# l_meter.net
KiCad netlist of a schematic drawn in EAGLE
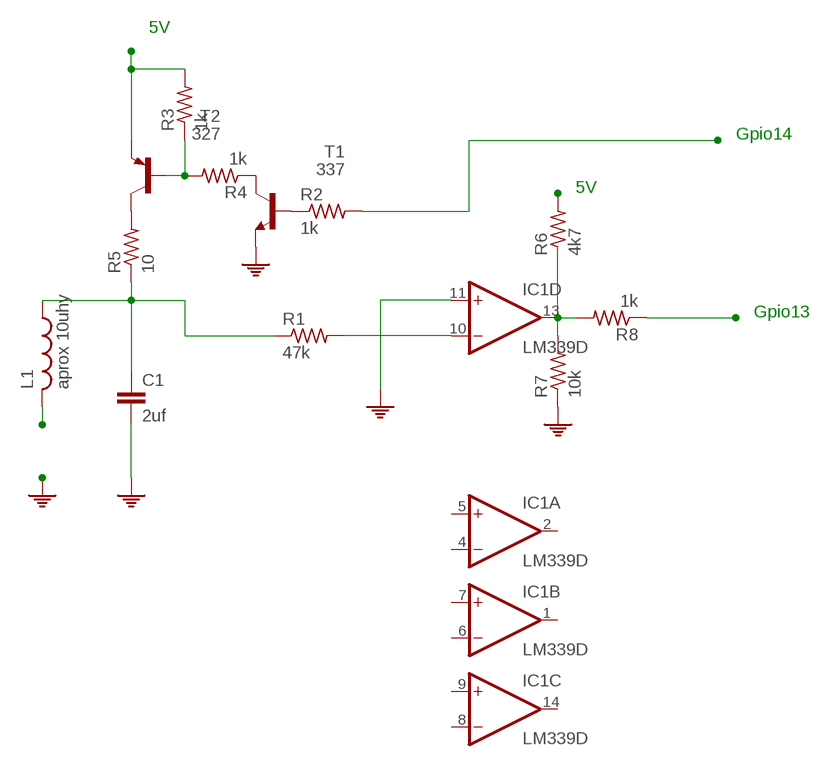
[diagram p0: schematic, sheet 1]

(export (version "E")
  (design (tool "Eeschema 10.0.6"))
  (components
    (comp (ref "C1")
      (value "2uf")
      (footprint "eagle-import:C025-030X050")
      (libsource (lib "eagle-import") (part "C-EU025-030X050"))
    )
    (comp (ref "IC1")
      (value "LM339D")
      (footprint "eagle-import:SO14")
      (libsource (lib "eagle-import") (part "LM339D"))
    )
    (comp (ref "L1")
      (value "aprox 10uhy")
      (footprint "eagle-import:IRF46")
      (libsource (lib "eagle-import") (part "L-USIRF-46"))
    )
    (comp (ref "R1")
      (value "47k")
      (footprint "eagle-import:0207_10")
      (libsource (lib "eagle-import") (part "R-US_0207/10"))
    )
    (comp (ref "R2")
      (value "1k")
      (footprint "eagle-import:0207_10")
      (libsource (lib "eagle-import") (part "R-US_0207/10"))
    )
    (comp (ref "R3")
      (value "1k")
      (footprint "eagle-import:0207_10")
      (libsource (lib "eagle-import") (part "R-US_0207/10"))
    )
    (comp (ref "R4")
      (value "1k")
      (footprint "eagle-import:0207_10")
      (libsource (lib "eagle-import") (part "R-US_0207/10"))
    )
    (comp (ref "R5")
      (value "10")
      (footprint "eagle-import:0207_10")
      (libsource (lib "eagle-import") (part "R-US_0207/10"))
    )
    (comp (ref "R6")
      (value "4k7")
      (footprint "eagle-import:0207_10")
      (libsource (lib "eagle-import") (part "R-US_0207/10"))
    )
    (comp (ref "R7")
      (value "10k")
      (footprint "eagle-import:0207_10")
      (libsource (lib "eagle-import") (part "R-US_0207/10"))
    )
    (comp (ref "R8")
      (value "1k")
      (footprint "eagle-import:0207_10")
      (libsource (lib "eagle-import") (part "R-US_0207/10"))
    )
    (comp (ref "T1")
      (value "337")
      (footprint "eagle-import:SOT23-EBC")
      (libsource (lib "eagle-import") (part "-NPN-SOT23-EBC"))
    )
    (comp (ref "T2")
      (value "327")
      (footprint "eagle-import:TO92")
      (libsource (lib "eagle-import") (part "-PNP-TO92"))
    )
  )
  (nets
    (net (code "1") (name "Net-(C1-Pad1)") (class "Default")
      (node (ref "C1") (pin "1") (pinfunction "1_1") (pintype "passive"))
      (node (ref "L1") (pin "1") (pinfunction "1_1") (pintype "passive"))
      (node (ref "R1") (pin "1") (pinfunction "1_1") (pintype "passive"))
      (node (ref "R5") (pin "1") (pinfunction "1_1") (pintype "passive"))
    )
    (net (code "2") (name "Net-(IC1D--IN)") (class "Default")
      (node (ref "IC1") (pin "10") (pinfunction "-IN_10") (pintype "input"))
      (node (ref "R1") (pin "2") (pinfunction "2_2") (pintype "passive"))
    )
    (net (code "3") (name "Net-(IC1D-OUT)") (class "Default")
      (node (ref "IC1") (pin "13") (pinfunction "OUT_13") (pintype "open_collector"))
      (node (ref "R7") (pin "2") (pinfunction "2_2") (pintype "passive"))
      (node (ref "R8") (pin "2") (pinfunction "2_2") (pintype "passive"))
    )
    (net (code "4") (name "Net-(R2-Pad1)") (class "Default")
      (node (ref "R2") (pin "1") (pinfunction "1_1") (pintype "passive"))
      (node (ref "T1") (pin "B") (pinfunction "B_B") (pintype "passive"))
    )
    (net (code "5") (name "Net-(R4-Pad1)") (class "Default")
      (node (ref "R4") (pin "1") (pinfunction "1_1") (pintype "passive"))
      (node (ref "T1") (pin "C") (pinfunction "C_C") (pintype "passive"))
    )
    (net (code "6") (name "Net-(T2-B)") (class "Default")
      (node (ref "R3") (pin "1") (pinfunction "1_1") (pintype "passive"))
      (node (ref "R4") (pin "2") (pinfunction "2_2") (pintype "passive"))
      (node (ref "T2") (pin "2") (pinfunction "B_2") (pintype "passive"))
    )
    (net (code "7") (name "Net-(T2-C)") (class "Default")
      (node (ref "R5") (pin "2") (pinfunction "2_2") (pintype "passive"))
      (node (ref "T2") (pin "3") (pinfunction "C_3") (pintype "passive"))
    )
    (net (code "8") (name "Net-(T2-E)") (class "Default")
      (node (ref "R3") (pin "2") (pinfunction "2_2") (pintype "passive"))
      (node (ref "T2") (pin "1") (pinfunction "E_1") (pintype "passive"))
    )
    (net (code "9") (name "PE") (class "Default")
      (node (ref "C1") (pin "2") (pinfunction "2_2") (pintype "passive"))
      (node (ref "IC1") (pin "11") (pinfunction "+IN_11") (pintype "input"))
      (node (ref "R7") (pin "1") (pinfunction "1_1") (pintype "passive"))
      (node (ref "T1") (pin "E") (pinfunction "E_E") (pintype "passive"))
    )
    (net (code "10") (name "unconnected-(IC1A-+IN-Pad5)") (class "Default")
      (node (ref "IC1") (pin "5") (pinfunction "+IN_5") (pintype "input"))
    )
    (net (code "11") (name "unconnected-(IC1A--IN-Pad4)") (class "Default")
      (node (ref "IC1") (pin "4") (pinfunction "-IN_4") (pintype "input"))
    )
    (net (code "12") (name "unconnected-(IC1A-OUT-Pad2)") (class "Default")
      (node (ref "IC1") (pin "2") (pinfunction "OUT_2") (pintype "open_collector"))
    )
    (net (code "13") (name "unconnected-(IC1B-+IN-Pad7)") (class "Default")
      (node (ref "IC1") (pin "7") (pinfunction "+IN_7") (pintype "input"))
    )
    (net (code "14") (name "unconnected-(IC1B--IN-Pad6)") (class "Default")
      (node (ref "IC1") (pin "6") (pinfunction "-IN_6") (pintype "input"))
    )
    (net (code "15") (name "unconnected-(IC1B-OUT-Pad1)") (class "Default")
      (node (ref "IC1") (pin "1") (pinfunction "OUT_1") (pintype "open_collector"))
    )
    (net (code "16") (name "unconnected-(IC1C-+IN-Pad9)") (class "Default")
      (node (ref "IC1") (pin "9") (pinfunction "+IN_9") (pintype "input"))
    )
    (net (code "17") (name "unconnected-(IC1C--IN-Pad8)") (class "Default")
      (node (ref "IC1") (pin "8") (pinfunction "-IN_8") (pintype "input"))
    )
    (net (code "18") (name "unconnected-(IC1C-OUT-Pad14)") (class "Default")
      (node (ref "IC1") (pin "14") (pinfunction "OUT_14") (pintype "open_collector"))
    )
    (net (code "19") (name "unconnected-(L1-Pad2)") (class "Default")
      (node (ref "L1") (pin "2") (pinfunction "2_2") (pintype "passive"))
    )
    (net (code "20") (name "unconnected-(R2-Pad2)") (class "Default")
      (node (ref "R2") (pin "2") (pinfunction "2_2") (pintype "passive"))
    )
    (net (code "21") (name "unconnected-(R6-Pad1)") (class "Default")
      (node (ref "R6") (pin "1") (pinfunction "1_1") (pintype "passive"))
    )
    (net (code "22") (name "unconnected-(R6-Pad2)") (class "Default")
      (node (ref "R6") (pin "2") (pinfunction "2_2") (pintype "passive"))
    )
    (net (code "23") (name "unconnected-(R8-Pad1)") (class "Default")
      (node (ref "R8") (pin "1") (pinfunction "1_1") (pintype "passive"))
    )
  )
)
